# TDBR_MCP3221.net
KiCad netlist of a schematic drawn in EAGLE
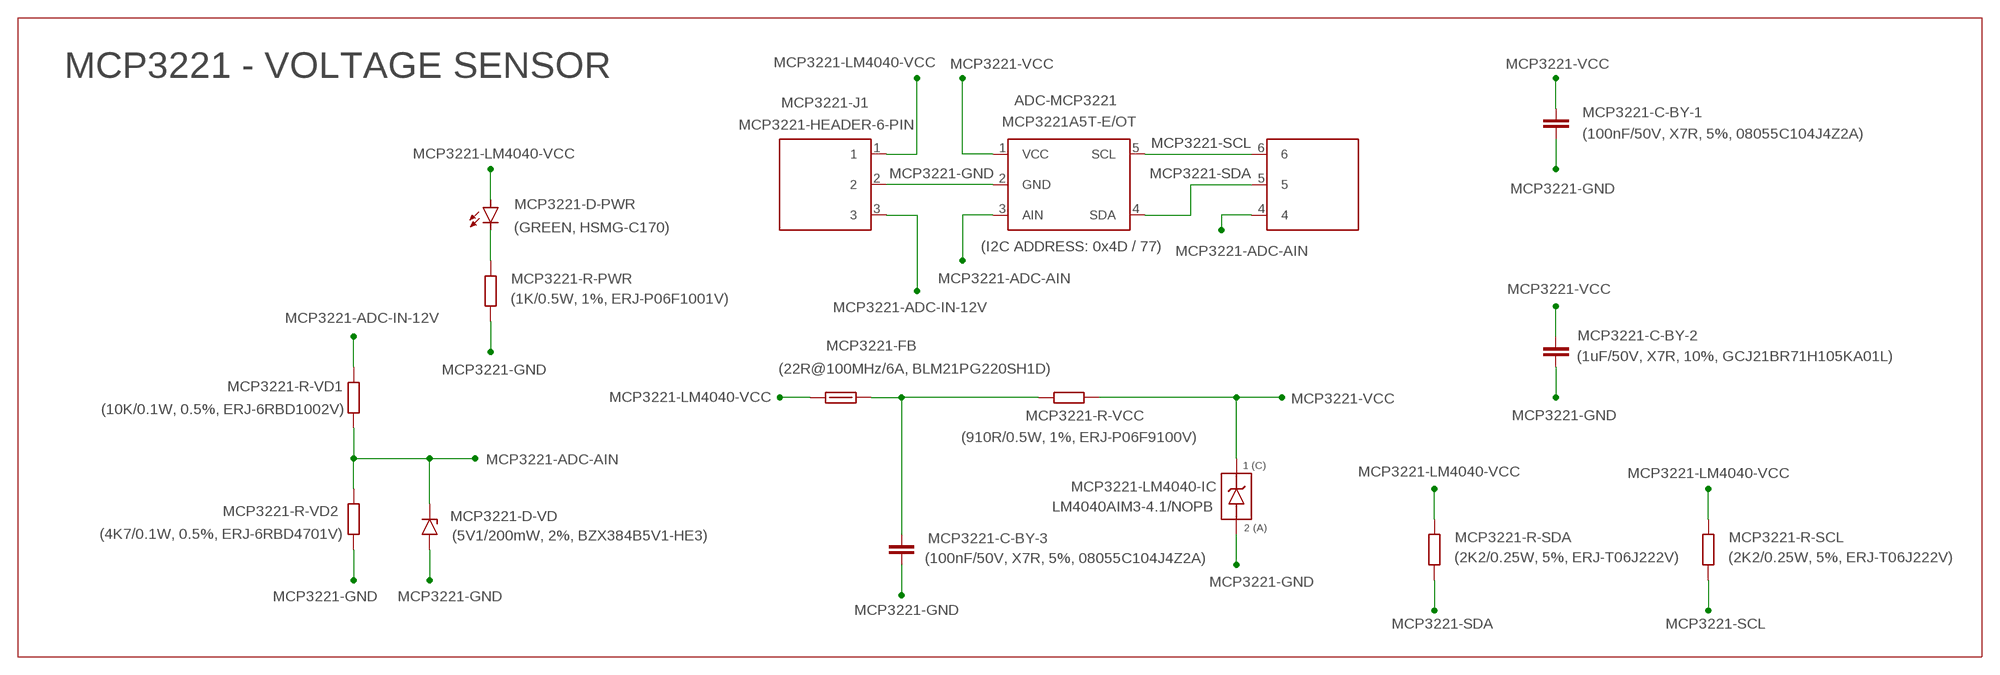
[diagram p0: schematic, sheet 1]

(export (version "E")
  (design (tool "Eeschema 10.0.6"))
  (components
    (comp (ref "ADC-MCP3221")
      (value "MCP3221A5T-E/OT")
      (footprint "eagle-import:SOT-23-5")
      (libsource (lib "eagle-import") (part "MCP3221A5T-E/OT"))
    )
    (comp (ref "MCP3221-C-BY-1")
      (value "(100nF/50V, X7R, 5%, 08055C104J4Z2A)")
      (footprint "eagle-import:0805")
      (libsource (lib "eagle-import") (part "08055C104J4Z2A"))
    )
    (comp (ref "MCP3221-C-BY-2")
      (value "(1uF/50V, X7R, 10%, GCJ21BR71H105KA01L)")
      (footprint "eagle-import:0805")
      (libsource (lib "eagle-import") (part "GCJ21BR71H105KA01L"))
    )
    (comp (ref "MCP3221-C-BY-3")
      (value "(100nF/50V, X7R, 5%, 08055C104J4Z2A)")
      (footprint "eagle-import:0805")
      (libsource (lib "eagle-import") (part "08055C104J4Z2A"))
    )
    (comp (ref "MCP3221-D-PWR")
      (value "(GREEN, HSMG-C170)")
      (footprint "eagle-import:DIODE_0805")
      (libsource (lib "eagle-import") (part "HSMG-C170"))
    )
    (comp (ref "MCP3221-D-VD")
      (value "(5V1/200mW, 2%, BZX384B5V1-HE3)")
      (footprint "eagle-import:SOD-323-DIODE")
      (libsource (lib "eagle-import") (part "BZX384B5V1-HE3"))
    )
    (comp (ref "MCP3221-FB")
      (value "(22R@100MHz/6A, BLM21PG220SH1D)")
      (footprint "eagle-import:0805")
      (libsource (lib "eagle-import") (part "BLM21PG220SH1D"))
    )
    (comp (ref "MCP3221-J1")
      (value "MCP3221-HEADER-6-PIN")
      (footprint "eagle-import:HEADER_2.54MM_6_PIN_VER")
      (libsource (lib "eagle-import") (part "HEADER_6_PIN"))
    )
    (comp (ref "MCP3221-LM4040-IC")
      (value "LM4040AIM3-4.1/NOPB")
      (footprint "eagle-import:SOT-23-3")
      (libsource (lib "eagle-import") (part "LM4040AIM3-4.1/NOPB"))
    )
    (comp (ref "MCP3221-R-PWR")
      (value "(1K/0.5W, 1%, ERJ-P06F1001V)")
      (footprint "eagle-import:0805")
      (libsource (lib "eagle-import") (part "ERJ-P06F1001V"))
    )
    (comp (ref "MCP3221-R-SCL")
      (value "(2K2/0.25W, 5%, ERJ-T06J222V)")
      (footprint "eagle-import:0805")
      (libsource (lib "eagle-import") (part "ERJ-T06J222V"))
    )
    (comp (ref "MCP3221-R-SDA")
      (value "(2K2/0.25W, 5%, ERJ-T06J222V)")
      (footprint "eagle-import:0805")
      (libsource (lib "eagle-import") (part "ERJ-T06J222V"))
    )
    (comp (ref "MCP3221-R-VCC")
      (value "(910R/0.5W, 1%, ERJ-P06F9100V)")
      (footprint "eagle-import:0805")
      (libsource (lib "eagle-import") (part "ERJ-P06F9100V"))
    )
    (comp (ref "MCP3221-R-VD1")
      (value "(10K/0.1W, 0.5%, ERJ-6RBD1002V)")
      (footprint "eagle-import:0805")
      (libsource (lib "eagle-import") (part "ERJ-6RBD1002V"))
    )
    (comp (ref "MCP3221-R-VD2")
      (value "(4K7/0.1W, 0.5%, ERJ-6RBD4701V)")
      (footprint "eagle-import:0805")
      (libsource (lib "eagle-import") (part "ERJ-6RBD4701V"))
    )
  )
  (nets
    (net (code "1") (name "/MCP3221-ADC-AIN") (class "Default")
      (node (ref "ADC-MCP3221") (pin "3") (pinfunction "AIN_3") (pintype "bidirectional"))
      (node (ref "MCP3221-D-VD") (pin "C") (pinfunction "C_C") (pintype "passive"))
      (node (ref "MCP3221-J1") (pin "4") (pinfunction "4_4") (pintype "bidirectional"))
      (node (ref "MCP3221-R-VD1") (pin "2") (pinfunction "2_2") (pintype "passive"))
      (node (ref "MCP3221-R-VD2") (pin "1") (pinfunction "1_1") (pintype "passive"))
    )
    (net (code "2") (name "/MCP3221-ADC-IN-12V") (class "Default")
      (node (ref "MCP3221-J1") (pin "3") (pinfunction "3_3") (pintype "bidirectional"))
      (node (ref "MCP3221-R-VD1") (pin "1") (pinfunction "1_1") (pintype "passive"))
    )
    (net (code "3") (name "/MCP3221-GND") (class "Default")
      (node (ref "ADC-MCP3221") (pin "2") (pinfunction "GND_2") (pintype "power_in"))
      (node (ref "MCP3221-C-BY-1") (pin "2") (pinfunction "C_2") (pintype "passive"))
      (node (ref "MCP3221-C-BY-2") (pin "1") (pinfunction "A_1") (pintype "passive"))
      (node (ref "MCP3221-C-BY-3") (pin "2") (pinfunction "C_2") (pintype "passive"))
      (node (ref "MCP3221-D-VD") (pin "A") (pinfunction "A_A") (pintype "passive"))
      (node (ref "MCP3221-J1") (pin "2") (pinfunction "2_2") (pintype "bidirectional"))
      (node (ref "MCP3221-LM4040-IC") (pin "2") (pinfunction "A_2") (pintype "passive"))
      (node (ref "MCP3221-LM4040-IC") (pin "3") (pinfunction "A_3") (pintype "passive"))
      (node (ref "MCP3221-R-PWR") (pin "1") (pinfunction "1_1") (pintype "passive"))
      (node (ref "MCP3221-R-VD2") (pin "2") (pinfunction "2_2") (pintype "passive"))
    )
    (net (code "4") (name "/MCP3221-LM4040-VCC") (class "Default")
      (node (ref "MCP3221-D-PWR") (pin "A") (pinfunction "A_A") (pintype "passive"))
      (node (ref "MCP3221-FB") (pin "2") (pinfunction "2_2") (pintype "passive"))
      (node (ref "MCP3221-J1") (pin "1") (pinfunction "1_1") (pintype "bidirectional"))
      (node (ref "MCP3221-R-SCL") (pin "2") (pinfunction "2_2") (pintype "passive"))
      (node (ref "MCP3221-R-SDA") (pin "2") (pinfunction "2_2") (pintype "passive"))
    )
    (net (code "5") (name "/MCP3221-SCL") (class "Default")
      (node (ref "ADC-MCP3221") (pin "5") (pinfunction "SCL_5") (pintype "bidirectional"))
      (node (ref "MCP3221-J1") (pin "6") (pinfunction "6_6") (pintype "bidirectional"))
      (node (ref "MCP3221-R-SCL") (pin "1") (pinfunction "1_1") (pintype "passive"))
    )
    (net (code "6") (name "/MCP3221-SDA") (class "Default")
      (node (ref "ADC-MCP3221") (pin "4") (pinfunction "SDA_4") (pintype "bidirectional"))
      (node (ref "MCP3221-J1") (pin "5") (pinfunction "5_5") (pintype "bidirectional"))
      (node (ref "MCP3221-R-SDA") (pin "1") (pinfunction "1_1") (pintype "passive"))
    )
    (net (code "7") (name "/MCP3221-VCC") (class "Default")
      (node (ref "ADC-MCP3221") (pin "1") (pinfunction "VCC_1") (pintype "power_in"))
      (node (ref "MCP3221-C-BY-1") (pin "1") (pinfunction "A_1") (pintype "passive"))
      (node (ref "MCP3221-C-BY-2") (pin "2") (pinfunction "C_2") (pintype "passive"))
      (node (ref "MCP3221-LM4040-IC") (pin "1") (pinfunction "C_1") (pintype "passive"))
      (node (ref "MCP3221-R-VCC") (pin "1") (pinfunction "1_1") (pintype "passive"))
    )
    (net (code "8") (name "Net-(MCP3221-C-BY-3-A)") (class "Default")
      (node (ref "MCP3221-C-BY-3") (pin "1") (pinfunction "A_1") (pintype "passive"))
      (node (ref "MCP3221-FB") (pin "1") (pinfunction "1_1") (pintype "passive"))
      (node (ref "MCP3221-R-VCC") (pin "2") (pinfunction "2_2") (pintype "passive"))
    )
    (net (code "9") (name "Net-(MCP3221-D-PWR-PadC)") (class "Default")
      (node (ref "MCP3221-D-PWR") (pin "C") (pinfunction "C_C") (pintype "passive"))
      (node (ref "MCP3221-R-PWR") (pin "2") (pinfunction "2_2") (pintype "passive"))
    )
  )
)
